# climbingRGB_bolt.net
KiCad netlist of a schematic drawn in EAGLE
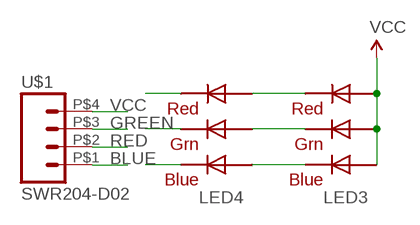
[diagram p0: schematic, sheet 1]

(export (version "E")
  (design (tool "Eeschema 10.0.6"))
  (components
    (comp (ref "LED3")
      (value "RGBLED5050")
      (footprint "eagle-import:RGBLED5050")
      (libsource (lib "eagle-import") (part "RGBLED5050"))
    )
    (comp (ref "LED4")
      (value "RGBLED5050")
      (footprint "eagle-import:RGBLED5050")
      (libsource (lib "eagle-import") (part "RGBLED5050"))
    )
    (comp (ref "U$1")
      (value "SWR204-D02")
      (footprint "eagle-import:SWR204")
      (libsource (lib "eagle-import") (part "SWR204-D02"))
    )
  )
  (nets
    (net (code "1") (name "/BLUE") (class "Default")
      (node (ref "LED4") (pin "4") (pinfunction "BLUE_C_4") (pintype "bidirectional"))
      (node (ref "U$1") (pin "P$1") (pinfunction "1_P$1") (pintype "passive"))
    )
    (net (code "2") (name "/GREEN") (class "Default")
      (node (ref "LED4") (pin "6") (pinfunction "GREEN_C_6") (pintype "bidirectional"))
      (node (ref "U$1") (pin "P$3") (pinfunction "3_P$3") (pintype "passive"))
    )
    (net (code "3") (name "/RED") (class "Default")
      (node (ref "LED4") (pin "5") (pinfunction "RED_C_5") (pintype "bidirectional"))
      (node (ref "U$1") (pin "P$2") (pinfunction "2_P$2") (pintype "passive"))
    )
    (net (code "4") (name "Net-(LED3-BLUE_C)") (class "Default")
      (node (ref "LED3") (pin "4") (pinfunction "BLUE_C_4") (pintype "bidirectional"))
      (node (ref "LED4") (pin "3") (pinfunction "BLUE_A_3") (pintype "bidirectional"))
    )
    (net (code "5") (name "Net-(LED3-GREEN_C)") (class "Default")
      (node (ref "LED3") (pin "6") (pinfunction "GREEN_C_6") (pintype "bidirectional"))
      (node (ref "LED4") (pin "1") (pinfunction "GREEN_A_1") (pintype "bidirectional"))
    )
    (net (code "6") (name "Net-(LED3-RED_C)") (class "Default")
      (node (ref "LED3") (pin "5") (pinfunction "RED_C_5") (pintype "bidirectional"))
      (node (ref "LED4") (pin "2") (pinfunction "RED_A_2") (pintype "bidirectional"))
    )
    (net (code "7") (name "VCC") (class "Default")
      (node (ref "LED3") (pin "1") (pinfunction "GREEN_A_1") (pintype "bidirectional"))
      (node (ref "LED3") (pin "2") (pinfunction "RED_A_2") (pintype "bidirectional"))
      (node (ref "LED3") (pin "3") (pinfunction "BLUE_A_3") (pintype "bidirectional"))
      (node (ref "U$1") (pin "P$4") (pinfunction "4_P$4") (pintype "passive"))
    )
  )
)
